# DC_5V.net
KiCad netlist of a schematic drawn in Altium Designer
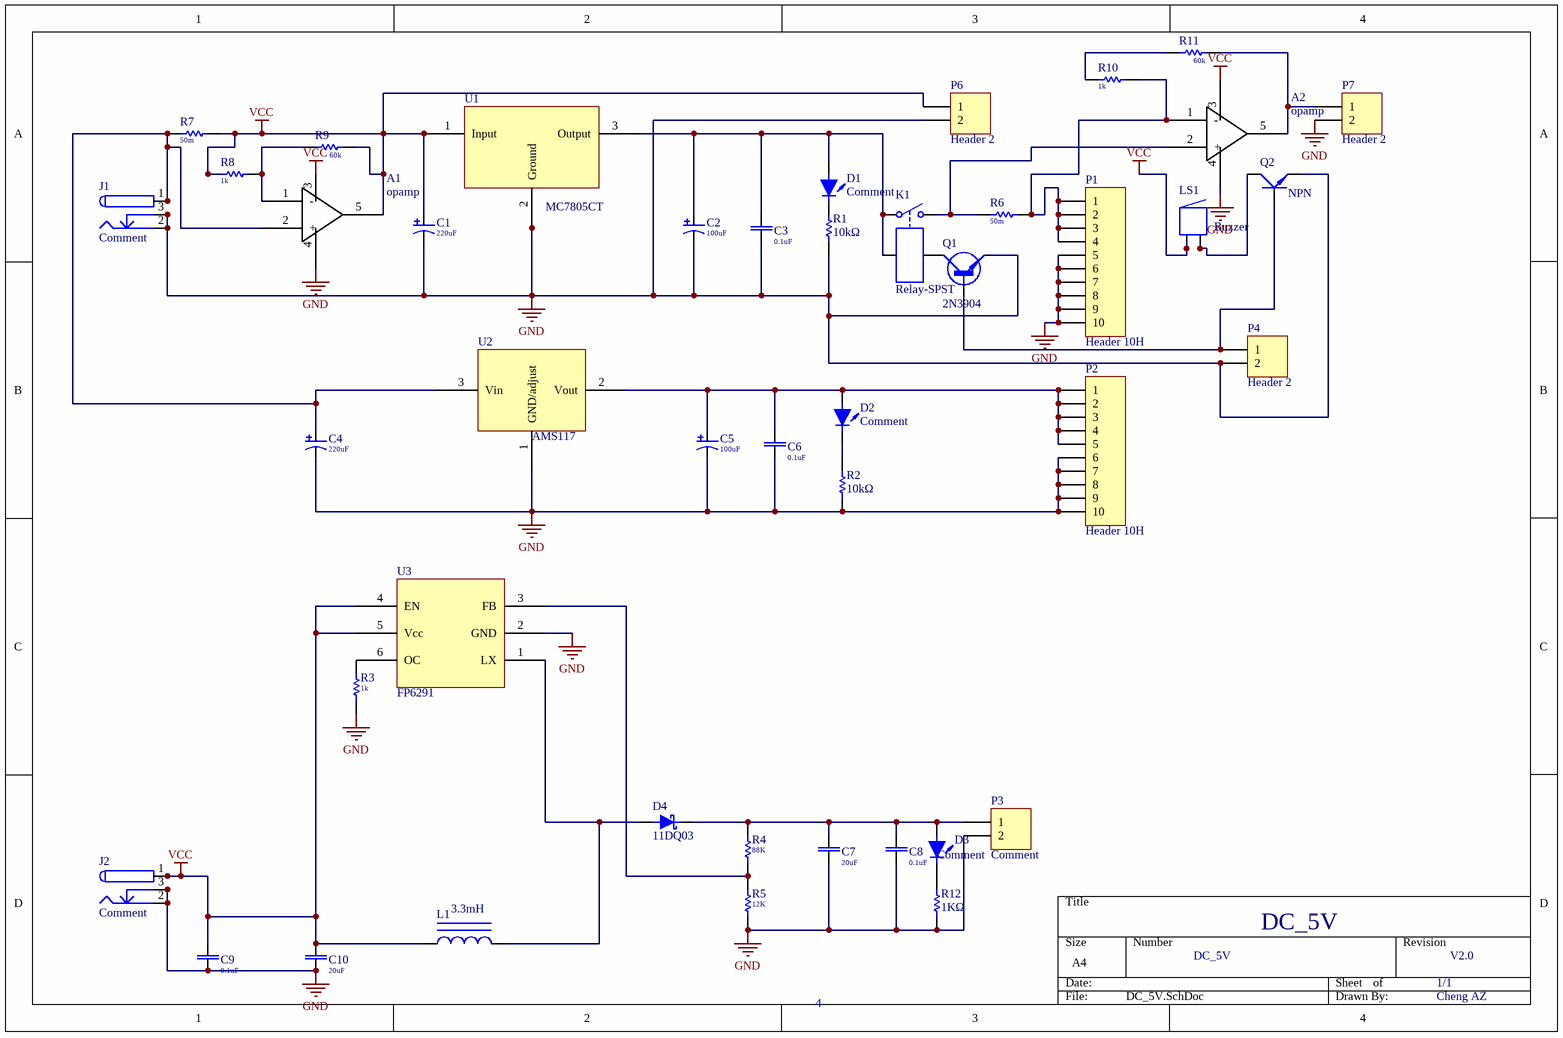
[diagram p0: DC_5V.SchDoc]

(export (version "E")
  (design (tool "Eeschema 10.0.6"))
  (components
    (comp (ref "A1") (value "opamp") (footprint "CAN_8/D_9") (libsource (lib "DC_5V") (part "opamp")))
    (comp (ref "A2") (value "opamp") (footprint "CAN_8/D_9") (libsource (lib "DC_5V") (part "opamp")))
    (comp (ref "C1")
      (value "220uF")
      (footprint "CAPPR1.27-1.7x2.8")
      (description "Polarized Capacitor (Axial)")
      (fields (field (name "Comment") "Comment") (field (name "PUBLISHER") "Altium Limited"))
      (libsource (lib "Miscellaneous Devices") (part "Cap Pol2"))
    )
    (comp (ref "C2")
      (value "100uF")
      (footprint "CAPPR1.27-1.7x2.8")
      (description "Polarized Capacitor (Axial)")
      (fields (field (name "Comment") "Comment") (field (name "PUBLISHER") "Altium Limited"))
      (libsource (lib "Miscellaneous Devices") (part "Cap Pol2"))
    )
    (comp (ref "C3")
      (value "0.1uF")
      (footprint "CAPC1005L")
      (description "Capacitor (Semiconductor SIM Model)")
      (fields (field (name "Comment") "Cap Semi") (field (name "PUBLISHER") "Altium Limited"))
      (libsource (lib "Miscellaneous Devices") (part "Cap Semi"))
    )
    (comp (ref "C4")
      (value "220uF")
      (footprint "CAPPR1.27-1.7x2.8")
      (description "Polarized Capacitor (Axial)")
      (fields (field (name "Comment") "Comment") (field (name "PUBLISHER") "Altium Limited"))
      (libsource (lib "Miscellaneous Devices") (part "Cap Pol2"))
    )
    (comp (ref "C5")
      (value "100uF")
      (footprint "CAPPR1.27-1.7x2.8")
      (description "Polarized Capacitor (Axial)")
      (fields (field (name "Comment") "Comment") (field (name "PUBLISHER") "Altium Limited"))
      (libsource (lib "Miscellaneous Devices") (part "Cap Pol2"))
    )
    (comp (ref "C6")
      (value "0.1uF")
      (footprint "CAPC1005L")
      (description "Capacitor (Semiconductor SIM Model)")
      (fields (field (name "Comment") "Cap Semi") (field (name "PUBLISHER") "Altium Limited"))
      (libsource (lib "Miscellaneous Devices") (part "Cap Semi"))
    )
    (comp (ref "C7")
      (value "20uF")
      (footprint "CAPC1005L")
      (description "Capacitor (Semiconductor SIM Model)")
      (fields (field (name "Comment") "Cap Semi") (field (name "PUBLISHER") "Altium Limited"))
      (libsource (lib "Miscellaneous Devices") (part "Cap Semi"))
    )
    (comp (ref "C8")
      (value "0.1uF")
      (footprint "CAPC1005L")
      (description "Capacitor (Semiconductor SIM Model)")
      (fields (field (name "Comment") "Cap Semi") (field (name "PUBLISHER") "Altium Limited"))
      (libsource (lib "Miscellaneous Devices") (part "Cap Semi"))
    )
    (comp (ref "C9")
      (value "0.1uF")
      (footprint "CAPC1005L")
      (description "Capacitor (Semiconductor SIM Model)")
      (fields (field (name "Comment") "Cap Semi") (field (name "PUBLISHER") "Altium Limited"))
      (libsource (lib "Miscellaneous Devices") (part "Cap Semi"))
    )
    (comp (ref "C10")
      (value "20uF")
      (footprint "CAPC1005L")
      (description "Capacitor (Semiconductor SIM Model)")
      (fields (field (name "Comment") "Cap Semi") (field (name "PUBLISHER") "Altium Limited"))
      (libsource (lib "Miscellaneous Devices") (part "Cap Semi"))
    )
    (comp (ref "D1")
      (value "Comment")
      (footprint "DSO-F2/D6.1")
      (description "Typical RED, GREEN, YELLOW, AMBER GaAs LED")
      (fields (field (name "PUBLISHER") "Altium Limited"))
      (libsource (lib "Miscellaneous Devices") (part "LED2"))
    )
    (comp (ref "D2")
      (value "Comment")
      (footprint "DSO-F2/D6.1")
      (description "Typical RED, GREEN, YELLOW, AMBER GaAs LED")
      (fields (field (name "PUBLISHER") "Altium Limited"))
      (libsource (lib "Miscellaneous Devices") (part "LED2"))
    )
    (comp (ref "D3")
      (value "Comment")
      (footprint "DSO-F2/D6.1")
      (description "Typical RED, GREEN, YELLOW, AMBER GaAs LED")
      (fields (field (name "PUBLISHER") "Altium Limited"))
      (libsource (lib "Miscellaneous Devices") (part "LED2"))
    )
    (comp (ref "D4")
      (value "11DQ03")
      (footprint "DIO10.46-5.3x2.8")
      (description "Schottky Rectifier")
      (fields (field (name "PUBLISHER") "Altium Limited"))
      (libsource (lib "Miscellaneous Devices") (part "Diode 11DQ03"))
    )
    (comp (ref "J1")
      (value "Comment")
      (footprint "KLD-0202")
      (description "Low Voltage Power Supply Connector")
      (fields (field (name "PUBLISHER") "Altium Limited"))
      (libsource (lib "Miscellaneous Connectors") (part "PWR2.5"))
    )
    (comp (ref "J2")
      (value "Comment")
      (footprint "KLD-0202")
      (description "Low Voltage Power Supply Connector")
      (fields (field (name "PUBLISHER") "Altium Limited"))
      (libsource (lib "Miscellaneous Connectors") (part "PWR2.5"))
    )
    (comp (ref "K1")
      (value "Relay-SPST")
      (footprint "DIP-P4")
      (description "Single-Pole Single-Throw Relay")
      (fields (field (name "PUBLISHER") "Altium Limited"))
      (libsource (lib "Miscellaneous Devices") (part "Relay-SPST"))
    )
    (comp (ref "L1")
      (value "3.3mH")
      (footprint "AXIAL-0.9")
      (description "Magnetic-Core Inductor")
      (fields (field (name "PUBLISHER") "Altium Limited"))
      (libsource (lib "Miscellaneous Devices") (part "Inductor Iron"))
    )
    (comp (ref "LS1")
      (value "Buzzer")
      (footprint "ABSM-1574")
      (description "Magnetic Transducer Buzzer")
      (fields (field (name "PUBLISHER") "Altium Limited"))
      (libsource (lib "Miscellaneous Devices") (part "Buzzer"))
    )
    (comp (ref "P1")
      (value "Header 10H")
      (footprint "HDR1X10H")
      (description "Header, 10-Pin, Right Angle")
      (fields (field (name "PUBLISHER") "Altium Limited"))
      (libsource (lib "Miscellaneous Connectors") (part "Header 10H"))
    )
    (comp (ref "P2")
      (value "Header 10H")
      (footprint "HDR1X10H")
      (description "Header, 10-Pin, Right Angle")
      (fields (field (name "PUBLISHER") "Altium Limited"))
      (libsource (lib "Miscellaneous Connectors") (part "Header 10H"))
    )
    (comp (ref "P3")
      (value "Comment")
      (footprint "HDR1X2")
      (description "Header, 2-Pin")
      (fields (field (name "PUBLISHER") "Altium Limited"))
      (libsource (lib "Miscellaneous Connectors") (part "Header 2"))
    )
    (comp (ref "P4")
      (value "Header 2")
      (footprint "HDR1X2")
      (description "Header, 2-Pin")
      (fields (field (name "PUBLISHER") "Altium Limited"))
      (libsource (lib "Miscellaneous Connectors") (part "Header 2"))
    )
    (comp (ref "P6")
      (value "Header 2")
      (footprint "HDR1X2")
      (description "Header, 2-Pin")
      (fields (field (name "PUBLISHER") "Altium Limited"))
      (libsource (lib "Miscellaneous Connectors") (part "Header 2"))
    )
    (comp (ref "P7")
      (value "Header 2")
      (footprint "HDR1X2")
      (description "Header, 2-Pin")
      (fields (field (name "PUBLISHER") "Altium Limited"))
      (libsource (lib "Miscellaneous Connectors") (part "Header 2"))
    )
    (comp (ref "Q1")
      (value "2N3904")
      (footprint "BCY-W3/E4")
      (description "NPN General Purpose Amplifier")
      (fields (field (name "PUBLISHER") "Altium Limited"))
      (libsource (lib "Miscellaneous Devices") (part "2N3904"))
    )
    (comp (ref "Q2")
      (value "NPN")
      (footprint "BCY-W3")
      (description "NPN Bipolar Transistor")
      (fields (field (name "PUBLISHER") "Altium Limited"))
      (libsource (lib "Miscellaneous Devices") (part "NPN"))
    )
    (comp (ref "R1")
      (value "10kΩ")
      (footprint "RES 0805N (2012)")
      (description "Semiconductor Resistor")
      (fields (field (name "Comment") "Comment") (field (name "PUBLISHER") "Altium Limited"))
      (libsource (lib "Miscellaneous Devices") (part "Res Semi"))
    )
    (comp (ref "R2")
      (value "10kΩ")
      (footprint "RES 0805N (2012)")
      (description "Semiconductor Resistor")
      (fields (field (name "Comment") "Comment") (field (name "PUBLISHER") "Altium Limited"))
      (libsource (lib "Miscellaneous Devices") (part "Res Semi"))
    )
    (comp (ref "R3")
      (value "1k")
      (footprint "RES 0805N (2012)")
      (description "Resistor")
      (fields (field (name "Comment") "Comment") (field (name "PUBLISHER") "Altium Limited"))
      (libsource (lib "Miscellaneous Devices") (part "Res1"))
    )
    (comp (ref "R4")
      (value "88K")
      (footprint "RES 0805N (2012)")
      (description "Resistor")
      (fields (field (name "Comment") "Comment") (field (name "PUBLISHER") "Altium Limited"))
      (libsource (lib "Miscellaneous Devices") (part "Res1"))
    )
    (comp (ref "R5")
      (value "12K")
      (footprint "RES 0805N (2012)")
      (description "Resistor")
      (fields (field (name "Comment") "Comment") (field (name "PUBLISHER") "Altium Limited"))
      (libsource (lib "Miscellaneous Devices") (part "Res1"))
    )
    (comp (ref "R6")
      (value "50m")
      (footprint "RES 0805N (2012)")
      (description "Resistor")
      (fields (field (name "PUBLISHER") "Altium Limited"))
      (libsource (lib "Miscellaneous Devices") (part "Res1"))
    )
    (comp (ref "R7")
      (value "50m")
      (footprint "RES 0805N (2012)")
      (description "Resistor")
      (fields (field (name "PUBLISHER") "Altium Limited"))
      (libsource (lib "Miscellaneous Devices") (part "Res1"))
    )
    (comp (ref "R8")
      (value "1k")
      (footprint "RES 0805N (2012)")
      (description "Resistor")
      (fields (field (name "PUBLISHER") "Altium Limited"))
      (libsource (lib "Miscellaneous Devices") (part "Res1"))
    )
    (comp (ref "R9")
      (value "60k")
      (footprint "RES 0805N (2012)")
      (description "Resistor")
      (fields (field (name "PUBLISHER") "Altium Limited"))
      (libsource (lib "Miscellaneous Devices") (part "Res1"))
    )
    (comp (ref "R10")
      (value "1k")
      (footprint "RES 0805N (2012)")
      (description "Resistor")
      (fields (field (name "PUBLISHER") "Altium Limited"))
      (libsource (lib "") (part "Res1_1"))
    )
    (comp (ref "R11")
      (value "60k")
      (footprint "RES 0805N (2012)")
      (description "Resistor")
      (fields (field (name "PUBLISHER") "Altium Limited"))
      (libsource (lib "Miscellaneous Devices") (part "Res1"))
    )
    (comp (ref "R12")
      (value "1KΩ")
      (footprint "RES 0805N (2012)")
      (description "Semiconductor Resistor")
      (fields (field (name "Comment") "Comment") (field (name "PUBLISHER") "Altium Limited"))
      (libsource (lib "Miscellaneous Devices") (part "Res Semi"))
    )
    (comp (ref "U1")
      (value "MC7805CT")
      (footprint "TO-220-3")
      (description "1.0A Positive Voltage Regulators")
      (libsource (lib "DC_5V") (part "MC7805CT"))
    )
    (comp (ref "U2")
      (value "AMS117")
      (footprint "TO-252")
      (description "1A output current and to operate  down to 1V input-to-output differential.")
      (libsource (lib "DC_5V") (part "AMS117-3.3"))
    )
    (comp (ref "U3")
      (value "FP6291")
      (footprint "TO-220-6")
      (description "1.0A Positive Voltage Regulator PWM")
      (libsource (lib "DC_5V") (part "FP6291"))
    )
  )
  (nets
    (net (code "1") (name "GND") (class "Default")
      (node (ref "A1") (pin "4") (pintype "passive"))
      (node (ref "A2") (pin "4") (pintype "passive"))
      (node (ref "C1") (pin "2") (pinfunction "2_2") (pintype "passive"))
      (node (ref "C10") (pin "2") (pinfunction "2_2") (pintype "passive"))
      (node (ref "C2") (pin "2") (pinfunction "2_2") (pintype "passive"))
      (node (ref "C3") (pin "2") (pinfunction "2_2") (pintype "passive"))
      (node (ref "C4") (pin "2") (pinfunction "2_2") (pintype "passive"))
      (node (ref "C5") (pin "2") (pinfunction "2_2") (pintype "passive"))
      (node (ref "C6") (pin "2") (pinfunction "2_2") (pintype "passive"))
      (node (ref "C7") (pin "2") (pinfunction "2_2") (pintype "passive"))
      (node (ref "C8") (pin "2") (pinfunction "2_2") (pintype "passive"))
      (node (ref "C9") (pin "2") (pinfunction "2_2") (pintype "passive"))
      (node (ref "J1") (pin "2") (pinfunction "2_2") (pintype "power_in"))
      (node (ref "J1") (pin "2A") (pinfunction "2A_2A") (pintype "power_in"))
      (node (ref "J1") (pin "2B") (pinfunction "2B_2B") (pintype "power_in"))
      (node (ref "J1") (pin "3") (pinfunction "3_3") (pintype "power_in"))
      (node (ref "J1") (pin "3A") (pinfunction "3A_3A") (pintype "power_in"))
      (node (ref "J1") (pin "3B") (pinfunction "3B_3B") (pintype "power_in"))
      (node (ref "J2") (pin "2") (pinfunction "2_2") (pintype "power_in"))
      (node (ref "J2") (pin "2A") (pinfunction "2A_2A") (pintype "power_in"))
      (node (ref "J2") (pin "2B") (pinfunction "2B_2B") (pintype "power_in"))
      (node (ref "J2") (pin "3") (pinfunction "3_3") (pintype "power_in"))
      (node (ref "J2") (pin "3A") (pinfunction "3A_3A") (pintype "power_in"))
      (node (ref "J2") (pin "3B") (pinfunction "3B_3B") (pintype "power_in"))
      (node (ref "P1") (pin "10") (pinfunction "10_10") (pintype "passive"))
      (node (ref "P1") (pin "5") (pinfunction "5_5") (pintype "passive"))
      (node (ref "P1") (pin "6") (pinfunction "6_6") (pintype "passive"))
      (node (ref "P1") (pin "7") (pinfunction "7_7") (pintype "passive"))
      (node (ref "P1") (pin "8") (pinfunction "8_8") (pintype "passive"))
      (node (ref "P1") (pin "9") (pinfunction "9_9") (pintype "passive"))
      (node (ref "P2") (pin "10") (pinfunction "10_10") (pintype "passive"))
      (node (ref "P2") (pin "6") (pinfunction "6_6") (pintype "passive"))
      (node (ref "P2") (pin "7") (pinfunction "7_7") (pintype "passive"))
      (node (ref "P2") (pin "8") (pinfunction "8_8") (pintype "passive"))
      (node (ref "P2") (pin "9") (pinfunction "9_9") (pintype "passive"))
      (node (ref "P3") (pin "2") (pinfunction "2_2") (pintype "passive"))
      (node (ref "P4") (pin "2") (pinfunction "2_2") (pintype "passive"))
      (node (ref "P6") (pin "2") (pinfunction "2_2") (pintype "passive"))
      (node (ref "P7") (pin "2") (pinfunction "2_2") (pintype "passive"))
      (node (ref "Q1") (pin "1") (pinfunction "E_1") (pintype "passive"))
      (node (ref "Q2") (pin "3") (pinfunction "E_3") (pintype "passive"))
      (node (ref "R1") (pin "1") (pinfunction "1_1") (pintype "passive"))
      (node (ref "R12") (pin "1") (pinfunction "1_1") (pintype "passive"))
      (node (ref "R2") (pin "1") (pinfunction "1_1") (pintype "passive"))
      (node (ref "R3") (pin "1") (pinfunction "1_1") (pintype "passive"))
      (node (ref "R5") (pin "1") (pinfunction "1_1") (pintype "passive"))
      (node (ref "U1") (pin "2") (pinfunction "Ground_2") (pintype "passive"))
      (node (ref "U2") (pin "1") (pinfunction "GND/adjust_1") (pintype "passive"))
      (node (ref "U3") (pin "2") (pinfunction "GND_2") (pintype "passive"))
    )
    (net (code "2") (name "Net-(A1-+)") (class "Default")
      (node (ref "A1") (pin "2") (pinfunction "+_2") (pintype "passive"))
      (node (ref "C4") (pin "1") (pinfunction "1_1") (pintype "passive"))
      (node (ref "J1") (pin "1") (pinfunction "1_1") (pintype "power_in"))
      (node (ref "J1") (pin "1A") (pinfunction "1A_1A") (pintype "power_in"))
      (node (ref "J1") (pin "1B") (pinfunction "1B_1B") (pintype "power_in"))
      (node (ref "R7") (pin "1") (pinfunction "1_1") (pintype "passive"))
      (node (ref "U2") (pin "3") (pinfunction "Vin_3") (pintype "passive"))
    )
    (net (code "3") (name "Net-(A1--)") (class "Default")
      (node (ref "A1") (pin "1") (pinfunction "-_1") (pintype "passive"))
      (node (ref "R8") (pin "2") (pinfunction "2_2") (pintype "passive"))
      (node (ref "R9") (pin "1") (pinfunction "1_1") (pintype "passive"))
    )
    (net (code "4") (name "Net-(A2-+)") (class "Default")
      (node (ref "A2") (pin "2") (pinfunction "+_2") (pintype "passive"))
      (node (ref "K1") (pin "2") (pinfunction "2_2") (pintype "passive"))
      (node (ref "R6") (pin "1") (pinfunction "1_1") (pintype "passive"))
    )
    (net (code "5") (name "Net-(A2--)") (class "Default")
      (node (ref "A2") (pin "1") (pinfunction "-_1") (pintype "passive"))
      (node (ref "P1") (pin "1") (pinfunction "1_1") (pintype "passive"))
      (node (ref "P1") (pin "2") (pinfunction "2_2") (pintype "passive"))
      (node (ref "P1") (pin "3") (pinfunction "3_3") (pintype "passive"))
      (node (ref "P1") (pin "4") (pinfunction "4_4") (pintype "passive"))
      (node (ref "R10") (pin "1") (pinfunction "1_1") (pintype "passive"))
      (node (ref "R6") (pin "2") (pinfunction "2_2") (pintype "passive"))
    )
    (net (code "6") (name "Net-(A2-Pad5)") (class "Default")
      (node (ref "A2") (pin "5") (pintype "passive"))
      (node (ref "P7") (pin "1") (pinfunction "1_1") (pintype "passive"))
      (node (ref "R11") (pin "2") (pinfunction "2_2") (pintype "passive"))
    )
    (net (code "7") (name "Net-(D1-A)") (class "Default")
      (node (ref "C2") (pin "1") (pinfunction "1_1") (pintype "passive"))
      (node (ref "C3") (pin "1") (pinfunction "1_1") (pintype "passive"))
      (node (ref "D1") (pin "1") (pinfunction "A_1") (pintype "passive"))
      (node (ref "K1") (pin "1") (pinfunction "1_1") (pintype "passive"))
      (node (ref "K1") (pin "3") (pinfunction "3_3") (pintype "passive"))
      (node (ref "U1") (pin "3") (pinfunction "Output_3") (pintype "passive"))
    )
    (net (code "8") (name "Net-(D2-A)") (class "Default")
      (node (ref "C5") (pin "1") (pinfunction "1_1") (pintype "passive"))
      (node (ref "C6") (pin "1") (pinfunction "1_1") (pintype "passive"))
      (node (ref "D2") (pin "1") (pinfunction "A_1") (pintype "passive"))
      (node (ref "P2") (pin "1") (pinfunction "1_1") (pintype "passive"))
      (node (ref "P2") (pin "2") (pinfunction "2_2") (pintype "passive"))
      (node (ref "P2") (pin "3") (pinfunction "3_3") (pintype "passive"))
      (node (ref "P2") (pin "4") (pinfunction "4_4") (pintype "passive"))
      (node (ref "P2") (pin "5") (pinfunction "5_5") (pintype "passive"))
      (node (ref "U2") (pin "2") (pinfunction "Vout_2") (pintype "passive"))
    )
    (net (code "9") (name "Net-(D2-K)") (class "Default")
      (node (ref "D2") (pin "2") (pinfunction "K_2") (pintype "passive"))
      (node (ref "R2") (pin "2") (pinfunction "2_2") (pintype "passive"))
    )
    (net (code "10") (name "Net-(D3-A)") (class "Default")
      (node (ref "C7") (pin "1") (pinfunction "1_1") (pintype "passive"))
      (node (ref "C8") (pin "1") (pinfunction "1_1") (pintype "passive"))
      (node (ref "D3") (pin "1") (pinfunction "A_1") (pintype "passive"))
      (node (ref "D4") (pin "2") (pinfunction "K_2") (pintype "passive"))
      (node (ref "P3") (pin "1") (pinfunction "1_1") (pintype "passive"))
      (node (ref "R4") (pin "2") (pinfunction "2_2") (pintype "passive"))
    )
    (net (code "11") (name "Net-(D3-K)") (class "Default")
      (node (ref "D3") (pin "2") (pinfunction "K_2") (pintype "passive"))
      (node (ref "R12") (pin "2") (pinfunction "2_2") (pintype "passive"))
    )
    (net (code "12") (name "Net-(D4-A)") (class "Default")
      (node (ref "D4") (pin "1") (pinfunction "A_1") (pintype "passive"))
      (node (ref "L1") (pin "2") (pinfunction "2_2") (pintype "passive"))
      (node (ref "U3") (pin "1") (pinfunction "LX_1") (pintype "passive"))
    )
    (net (code "13") (name "Net-(Q1-B)") (class "Default")
      (node (ref "P4") (pin "1") (pinfunction "1_1") (pintype "passive"))
      (node (ref "Q1") (pin "2") (pinfunction "B_2") (pintype "passive"))
      (node (ref "Q2") (pin "2") (pinfunction "B_2") (pintype "passive"))
    )
    (net (code "14") (name "Net-(Q1-C)") (class "Default")
      (node (ref "K1") (pin "4") (pinfunction "4_4") (pintype "passive"))
      (node (ref "Q1") (pin "3") (pinfunction "C_3") (pintype "passive"))
    )
    (net (code "15") (name "Net-(Q2-C)") (class "Default")
      (node (ref "LS1") (pin "2") (pinfunction "2_2") (pintype "passive"))
      (node (ref "LS1") (pin "2A") (pinfunction "2A_2A") (pintype "passive"))
      (node (ref "Q2") (pin "1") (pinfunction "C_1") (pintype "passive"))
    )
    (net (code "16") (name "Net-(R10-Pad2)") (class "Default")
      (node (ref "R10") (pin "2") (pinfunction "2_2") (pintype "passive"))
      (node (ref "R11") (pin "1") (pinfunction "1_1") (pintype "passive"))
    )
    (net (code "17") (name "Net-(U3-FB)") (class "Default")
      (node (ref "R4") (pin "1") (pinfunction "1_1") (pintype "passive"))
      (node (ref "R5") (pin "2") (pinfunction "2_2") (pintype "passive"))
      (node (ref "U3") (pin "3") (pinfunction "FB_3") (pintype "passive"))
    )
    (net (code "18") (name "Net-(U3-OC)") (class "Default")
      (node (ref "R3") (pin "2") (pinfunction "2_2") (pintype "passive"))
      (node (ref "U3") (pin "6") (pinfunction "OC_6") (pintype "passive"))
    )
    (net (code "19") (name "VCC") (class "Default")
      (node (ref "A1") (pin "5") (pintype "passive"))
      (node (ref "A2") (pin "3") (pintype "passive"))
      (node (ref "C1") (pin "1") (pinfunction "1_1") (pintype "passive"))
      (node (ref "C10") (pin "1") (pinfunction "1_1") (pintype "passive"))
      (node (ref "C9") (pin "1") (pinfunction "1_1") (pintype "passive"))
      (node (ref "J2") (pin "1") (pinfunction "1_1") (pintype "power_in"))
      (node (ref "J2") (pin "1A") (pinfunction "1A_1A") (pintype "power_in"))
      (node (ref "J2") (pin "1B") (pinfunction "1B_1B") (pintype "power_in"))
      (node (ref "L1") (pin "1") (pinfunction "1_1") (pintype "passive"))
      (node (ref "LS1") (pin "1") (pinfunction "1_1") (pintype "passive"))
      (node (ref "LS1") (pin "1A") (pinfunction "1A_1A") (pintype "passive"))
      (node (ref "P6") (pin "1") (pinfunction "1_1") (pintype "passive"))
      (node (ref "R7") (pin "2") (pinfunction "2_2") (pintype "passive"))
      (node (ref "R8") (pin "1") (pinfunction "1_1") (pintype "passive"))
      (node (ref "R9") (pin "2") (pinfunction "2_2") (pintype "passive"))
      (node (ref "U1") (pin "1") (pinfunction "Input_1") (pintype "passive"))
      (node (ref "U3") (pin "4") (pinfunction "EN_4") (pintype "passive"))
      (node (ref "U3") (pin "5") (pinfunction "Vcc_5") (pintype "passive"))
    )
    (net (code "20") (name "unconnected-(A1-Pad3)") (class "Default")
      (node (ref "A1") (pin "3") (pintype "passive"))
    )
    (net (code "21") (name "unconnected-(D1-K-Pad2)") (class "Default")
      (node (ref "D1") (pin "2") (pinfunction "K_2") (pintype "passive"))
    )
    (net (code "22") (name "unconnected-(R1-Pad2)") (class "Default")
      (node (ref "R1") (pin "2") (pinfunction "2_2") (pintype "passive"))
    )
  )
)
